# MCU.net
KiCad netlist of a schematic drawn in Altium Designer
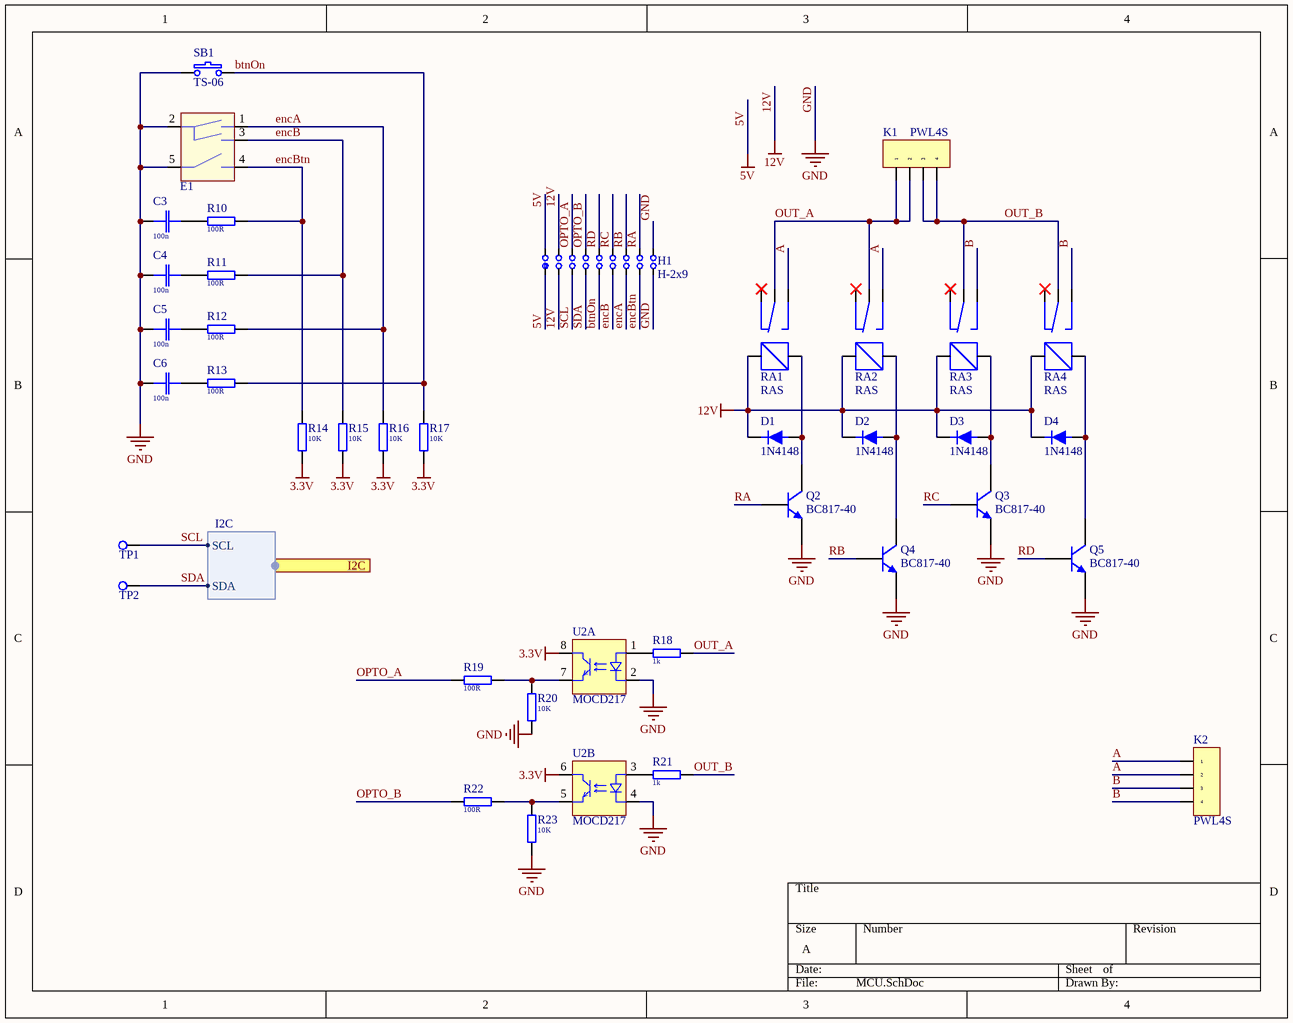
[diagram p0: MCU.SchDoc]

(export (version "E")
  (design (tool "Eeschema 10.0.6"))
  (components
    (comp (ref "C3")
      (value "100n")
      (footprint "C0805(2013)")
      (description "SMD-0805 50V Y5V +80/-20%")
      (libsource (lib "SMD-RCL") (part "C-0805   50V 100n"))
    )
    (comp (ref "C4")
      (value "100n")
      (footprint "C0805(2013)")
      (description "SMD-0805 50V Y5V +80/-20%")
      (libsource (lib "SMD-RCL") (part "C-0805   50V 100n"))
    )
    (comp (ref "C5")
      (value "100n")
      (footprint "C0805(2013)")
      (description "SMD-0805 50V Y5V +80/-20%")
      (libsource (lib "SMD-RCL") (part "C-0805   50V 100n"))
    )
    (comp (ref "C6")
      (value "100n")
      (footprint "C0805(2013)")
      (description "SMD-0805 50V Y5V +80/-20%")
      (libsource (lib "SMD-RCL") (part "C-0805   50V 100n"))
    )
    (comp (ref "D1")
      (value "1N4148")
      (footprint "DO-214AC (SMA)")
      (description "DO-35 75V 0.2A 1uS 4A 4nS")
      (libsource (lib "Diodes") (part "1N4148"))
    )
    (comp (ref "D2")
      (value "1N4148")
      (footprint "DO-214AC (SMA)")
      (description "DO-35 75V 0.2A 1uS 4A 4nS")
      (libsource (lib "Diodes") (part "1N4148"))
    )
    (comp (ref "D3")
      (value "1N4148")
      (footprint "DO-214AC (SMA)")
      (description "DO-35 75V 0.2A 1uS 4A 4nS")
      (libsource (lib "Diodes") (part "1N4148"))
    )
    (comp (ref "D4")
      (value "1N4148")
      (footprint "DO-214AC (SMA)")
      (description "DO-35 75V 0.2A 1uS 4A 4nS")
      (libsource (lib "Diodes") (part "1N4148"))
    )
    (comp (ref "E1")
      (value "Encoder SW")
      (footprint "PEC12")
      (description "Mechanical encoder with switch")
      (fields (field (name "PUBLISHER") "Altium Limited"))
      (libsource (lib "Mechanical") (part "Encoder SW"))
    )
    (comp (ref "H1") (value "H-2x9") (footprint "J2x9") (libsource (lib "Connektor") (part "H-2x9")))
    (comp (ref "K1")
      (value "PWL4S")
      (footprint "PWL4S")
      (description "3.96mm 7A/250V")
      (libsource (lib "Connektor") (part "PWL4S"))
    )
    (comp (ref "K2")
      (value "PWL4S")
      (footprint "PWL4S")
      (description "3.96mm 7A/250V")
      (libsource (lib "") (part "PWL4S_1"))
    )
    (comp (ref "Q2")
      (value "BC817-40")
      (footprint "SOT23_N")
      (description "NPN General-purpose Transistor")
      (fields (field (name "PUBLISHER") "Altium Limited"))
      (libsource (lib "Philips Discrete BJT - Low Power") (part "BC817-40"))
    )
    (comp (ref "Q3")
      (value "BC817-40")
      (footprint "SOT23_N")
      (description "NPN General-purpose Transistor")
      (fields (field (name "PUBLISHER") "Altium Limited"))
      (libsource (lib "Philips Discrete BJT - Low Power") (part "BC817-40"))
    )
    (comp (ref "Q4")
      (value "BC817-40")
      (footprint "SOT23_N")
      (description "NPN General-purpose Transistor")
      (fields (field (name "PUBLISHER") "Altium Limited"))
      (libsource (lib "Philips Discrete BJT - Low Power") (part "BC817-40"))
    )
    (comp (ref "Q5")
      (value "BC817-40")
      (footprint "SOT23_N")
      (description "NPN General-purpose Transistor")
      (fields (field (name "PUBLISHER") "Altium Limited"))
      (libsource (lib "Philips Discrete BJT - Low Power") (part "BC817-40"))
    )
    (comp (ref "R10")
      (value "100R")
      (footprint "R0805")
      (description "SMD 0805 0.1W 5% 150V")
      (libsource (lib "SMD-RCL") (part "R-0805"))
    )
    (comp (ref "R11")
      (value "100R")
      (footprint "R0805")
      (description "SMD 0805 0.1W 5% 150V")
      (libsource (lib "SMD-RCL") (part "R-0805"))
    )
    (comp (ref "R12")
      (value "100R")
      (footprint "R0805")
      (description "SMD 0805 0.1W 5% 150V")
      (libsource (lib "SMD-RCL") (part "R-0805"))
    )
    (comp (ref "R13")
      (value "100R")
      (footprint "R0805")
      (description "SMD 0805 0.1W 5% 150V")
      (libsource (lib "SMD-RCL") (part "R-0805"))
    )
    (comp (ref "R14")
      (value "10K")
      (footprint "R0805")
      (description "SMD 0805 0.1W 5% 150V")
      (libsource (lib "SMD-RCL") (part "R-0805"))
    )
    (comp (ref "R15")
      (value "10K")
      (footprint "R0805")
      (description "SMD 0805 0.1W 5% 150V")
      (libsource (lib "SMD-RCL") (part "R-0805"))
    )
    (comp (ref "R16")
      (value "10K")
      (footprint "R0805")
      (description "SMD 0805 0.1W 5% 150V")
      (libsource (lib "SMD-RCL") (part "R-0805"))
    )
    (comp (ref "R17")
      (value "10K")
      (footprint "R0805")
      (description "SMD 0805 0.1W 5% 150V")
      (libsource (lib "SMD-RCL") (part "R-0805"))
    )
    (comp (ref "R18")
      (value "1k")
      (footprint "R0805")
      (description "SMD 0805 0.1W 5% 150V")
      (libsource (lib "SMD-RCL") (part "R-0805"))
    )
    (comp (ref "R19")
      (value "100R")
      (footprint "R0805")
      (description "SMD 0805 0.1W 5% 150V")
      (libsource (lib "SMD-RCL") (part "R-0805"))
    )
    (comp (ref "R20")
      (value "10K")
      (footprint "R0805")
      (description "SMD 0805 0.1W 5% 150V")
      (libsource (lib "SMD-RCL") (part "R-0805"))
    )
    (comp (ref "R21")
      (value "1k")
      (footprint "R0805")
      (description "SMD 0805 0.1W 5% 150V")
      (libsource (lib "SMD-RCL") (part "R-0805"))
    )
    (comp (ref "R22")
      (value "100R")
      (footprint "R0805")
      (description "SMD 0805 0.1W 5% 150V")
      (libsource (lib "SMD-RCL") (part "R-0805"))
    )
    (comp (ref "R23")
      (value "10K")
      (footprint "R0805")
      (description "SMD 0805 0.1W 5% 150V")
      (libsource (lib "SMD-RCL") (part "R-0805"))
    )
    (comp (ref "RA1")
      (value "RAS")
      (footprint "Rele RAS")
      (description "AC-120V 15A DC-14V 20A 30V 15A /0.36W")
      (libsource (lib "Devise") (part "Relay RAS"))
    )
    (comp (ref "RA2")
      (value "RAS")
      (footprint "Rele RAS")
      (description "AC-120V 15A DC-14V 20A 30V 15A /0.36W")
      (libsource (lib "Devise") (part "Relay RAS"))
    )
    (comp (ref "RA3")
      (value "RAS")
      (footprint "Rele RAS")
      (description "AC-120V 15A DC-14V 20A 30V 15A /0.36W")
      (libsource (lib "Devise") (part "Relay RAS"))
    )
    (comp (ref "RA4")
      (value "RAS")
      (footprint "Rele RAS")
      (description "AC-120V 15A DC-14V 20A 30V 15A /0.36W")
      (libsource (lib "Devise") (part "Relay RAS"))
    )
    (comp (ref "SB1") (value "TS-06") (footprint "TS-06") (libsource (lib "Devise") (part "Buton TS-06")))
    (comp (ref "TP1")
      (value "TP")
      (footprint "TP_TH")
      (description "Test point")
      (libsource (lib "Mechanical") (part "TP"))
    )
    (comp (ref "TP2")
      (value "TP")
      (footprint "TP_TH")
      (description "Test point")
      (libsource (lib "Mechanical") (part "TP"))
    )
    (comp (ref "U2")
      (value "MOCD217")
      (footprint "SO-8 (MOCD217)")
      (description "Dual optocouple")
      (libsource (lib "Opto") (part "MOCD217"))
    )
  )
  (nets
    (net (code "2") (name "/A") (class "Default")
      (node (ref "K2") (pin "1") (pinfunction "1_1") (pintype "passive"))
      (node (ref "K2") (pin "2") (pinfunction "2_2") (pintype "passive"))
      (node (ref "RA1") (pin "5") (pinfunction "NO_5") (pintype "passive"))
      (node (ref "RA2") (pin "5") (pinfunction "NO_5") (pintype "passive"))
    )
    (net (code "3") (name "/B") (class "Default")
      (node (ref "K2") (pin "3") (pinfunction "3_3") (pintype "passive"))
      (node (ref "K2") (pin "4") (pinfunction "4_4") (pintype "passive"))
      (node (ref "RA3") (pin "5") (pinfunction "NO_5") (pintype "passive"))
      (node (ref "RA4") (pin "5") (pinfunction "NO_5") (pintype "passive"))
    )
    (net (code "4") (name "/OPTO_A") (class "Default")
      (node (ref "H1") (pin "6") (pinfunction "6_6") (pintype "passive"))
      (node (ref "R19") (pin "2") (pinfunction "2_2") (pintype "passive"))
    )
    (net (code "5") (name "/OPTO_B") (class "Default")
      (node (ref "H1") (pin "8") (pinfunction "8_8") (pintype "passive"))
      (node (ref "R22") (pin "2") (pinfunction "2_2") (pintype "passive"))
    )
    (net (code "6") (name "/OUT_A") (class "Default")
      (node (ref "K1") (pin "1") (pinfunction "1_1") (pintype "passive"))
      (node (ref "K1") (pin "2") (pinfunction "2_2") (pintype "passive"))
      (node (ref "R18") (pin "1") (pinfunction "1_1") (pintype "passive"))
      (node (ref "RA1") (pin "4") (pinfunction "O_4") (pintype "passive"))
      (node (ref "RA2") (pin "4") (pinfunction "O_4") (pintype "passive"))
    )
    (net (code "7") (name "/OUT_B") (class "Default")
      (node (ref "K1") (pin "3") (pinfunction "3_3") (pintype "passive"))
      (node (ref "K1") (pin "4") (pinfunction "4_4") (pintype "passive"))
      (node (ref "R21") (pin "1") (pinfunction "1_1") (pintype "passive"))
      (node (ref "RA3") (pin "4") (pinfunction "O_4") (pintype "passive"))
      (node (ref "RA4") (pin "4") (pinfunction "O_4") (pintype "passive"))
    )
    (net (code "8") (name "/RA") (class "Default")
      (node (ref "H1") (pin "16") (pinfunction "16_16") (pintype "passive"))
      (node (ref "Q2") (pin "1") (pinfunction "B_1") (pintype "passive"))
    )
    (net (code "9") (name "/RB") (class "Default")
      (node (ref "H1") (pin "14") (pinfunction "14_14") (pintype "passive"))
      (node (ref "Q4") (pin "1") (pinfunction "B_1") (pintype "passive"))
    )
    (net (code "10") (name "/RC") (class "Default")
      (node (ref "H1") (pin "12") (pinfunction "12_12") (pintype "passive"))
      (node (ref "Q3") (pin "1") (pinfunction "B_1") (pintype "passive"))
    )
    (net (code "11") (name "/RD") (class "Default")
      (node (ref "H1") (pin "10") (pinfunction "10_10") (pintype "passive"))
      (node (ref "Q5") (pin "1") (pinfunction "B_1") (pintype "passive"))
    )
    (net (code "12") (name "/SCL") (class "Default")
      (node (ref "H1") (pin "5") (pinfunction "5_5") (pintype "passive"))
      (node (ref "TP1") (pin "1") (pintype "passive"))
    )
    (net (code "13") (name "/SDA") (class "Default")
      (node (ref "H1") (pin "7") (pinfunction "7_7") (pintype "passive"))
      (node (ref "TP2") (pin "1") (pintype "passive"))
    )
    (net (code "14") (name "/btnOn") (class "Default")
      (node (ref "H1") (pin "9") (pinfunction "9_9") (pintype "passive"))
      (node (ref "R13") (pin "1") (pinfunction "1_1") (pintype "passive"))
      (node (ref "R17") (pin "2") (pinfunction "2_2") (pintype "passive"))
      (node (ref "SB1") (pin "2") (pinfunction "2_2") (pintype "passive"))
    )
    (net (code "15") (name "/encA") (class "Default")
      (node (ref "E1") (pin "1") (pinfunction "1_1") (pintype "passive"))
      (node (ref "H1") (pin "13") (pinfunction "13_13") (pintype "passive"))
      (node (ref "R12") (pin "1") (pinfunction "1_1") (pintype "passive"))
      (node (ref "R16") (pin "2") (pinfunction "2_2") (pintype "passive"))
    )
    (net (code "16") (name "/encB") (class "Default")
      (node (ref "E1") (pin "3") (pinfunction "3_3") (pintype "passive"))
      (node (ref "H1") (pin "11") (pinfunction "11_11") (pintype "passive"))
      (node (ref "R11") (pin "1") (pinfunction "1_1") (pintype "passive"))
      (node (ref "R15") (pin "2") (pinfunction "2_2") (pintype "passive"))
    )
    (net (code "17") (name "/encBtn") (class "Default")
      (node (ref "E1") (pin "4") (pinfunction "4_4") (pintype "passive"))
      (node (ref "H1") (pin "15") (pinfunction "15_15") (pintype "passive"))
      (node (ref "R10") (pin "1") (pinfunction "1_1") (pintype "passive"))
      (node (ref "R14") (pin "2") (pinfunction "2_2") (pintype "passive"))
    )
    (net (code "19") (name "3.3V") (class "Default")
      (node (ref "R14") (pin "1") (pinfunction "1_1") (pintype "passive"))
      (node (ref "R15") (pin "1") (pinfunction "1_1") (pintype "passive"))
      (node (ref "R16") (pin "1") (pinfunction "1_1") (pintype "passive"))
      (node (ref "R17") (pin "1") (pinfunction "1_1") (pintype "passive"))
      (node (ref "U2") (pin "6") (pinfunction "C_6") (pintype "passive"))
      (node (ref "U2") (pin "8") (pinfunction "C_8") (pintype "passive"))
    )
    (net (code "20") (name "5V") (class "Default")
      (node (ref "H1") (pin "1") (pinfunction "1_1") (pintype "passive"))
      (node (ref "H1") (pin "2") (pinfunction "2_2") (pintype "passive"))
    )
    (net (code "21") (name "12V") (class "Default")
      (node (ref "D1") (pin "2") (pinfunction "C_2") (pintype "passive"))
      (node (ref "D2") (pin "2") (pinfunction "C_2") (pintype "passive"))
      (node (ref "D3") (pin "2") (pinfunction "C_2") (pintype "passive"))
      (node (ref "D4") (pin "2") (pinfunction "C_2") (pintype "passive"))
      (node (ref "H1") (pin "3") (pinfunction "3_3") (pintype "passive"))
      (node (ref "H1") (pin "4") (pinfunction "4_4") (pintype "passive"))
      (node (ref "RA1") (pin "1") (pinfunction "a_1") (pintype "passive"))
      (node (ref "RA2") (pin "1") (pinfunction "a_1") (pintype "passive"))
      (node (ref "RA3") (pin "1") (pinfunction "a_1") (pintype "passive"))
      (node (ref "RA4") (pin "1") (pinfunction "a_1") (pintype "passive"))
    )
    (net (code "22") (name "GND") (class "Default")
      (node (ref "C3") (pin "2") (pinfunction "2_2") (pintype "passive"))
      (node (ref "C4") (pin "2") (pinfunction "2_2") (pintype "passive"))
      (node (ref "C5") (pin "2") (pinfunction "2_2") (pintype "passive"))
      (node (ref "C6") (pin "2") (pinfunction "2_2") (pintype "passive"))
      (node (ref "E1") (pin "2") (pinfunction "2_2") (pintype "passive"))
      (node (ref "E1") (pin "5") (pinfunction "5_5") (pintype "passive"))
      (node (ref "H1") (pin "17") (pinfunction "17_17") (pintype "passive"))
      (node (ref "H1") (pin "18") (pinfunction "18_18") (pintype "passive"))
      (node (ref "Q2") (pin "2") (pinfunction "E_2") (pintype "passive"))
      (node (ref "Q3") (pin "2") (pinfunction "E_2") (pintype "passive"))
      (node (ref "Q4") (pin "2") (pinfunction "E_2") (pintype "passive"))
      (node (ref "Q5") (pin "2") (pinfunction "E_2") (pintype "passive"))
      (node (ref "R20") (pin "2") (pinfunction "2_2") (pintype "passive"))
      (node (ref "R23") (pin "1") (pinfunction "1_1") (pintype "passive"))
      (node (ref "SB1") (pin "1") (pinfunction "1_1") (pintype "passive"))
      (node (ref "U2") (pin "2") (pinfunction "K_2") (pintype "passive"))
      (node (ref "U2") (pin "4") (pinfunction "K_4") (pintype "passive"))
    )
    (net (code "23") (name "Net-(C3-Pad1)") (class "Default")
      (node (ref "C3") (pin "1") (pinfunction "1_1") (pintype "passive"))
      (node (ref "R10") (pin "2") (pinfunction "2_2") (pintype "passive"))
    )
    (net (code "24") (name "Net-(C4-Pad1)") (class "Default")
      (node (ref "C4") (pin "1") (pinfunction "1_1") (pintype "passive"))
      (node (ref "R11") (pin "2") (pinfunction "2_2") (pintype "passive"))
    )
    (net (code "25") (name "Net-(C5-Pad1)") (class "Default")
      (node (ref "C5") (pin "1") (pinfunction "1_1") (pintype "passive"))
      (node (ref "R12") (pin "2") (pinfunction "2_2") (pintype "passive"))
    )
    (net (code "26") (name "Net-(C6-Pad1)") (class "Default")
      (node (ref "C6") (pin "1") (pinfunction "1_1") (pintype "passive"))
      (node (ref "R13") (pin "2") (pinfunction "2_2") (pintype "passive"))
    )
    (net (code "27") (name "Net-(D1-A)") (class "Default")
      (node (ref "D1") (pin "1") (pinfunction "A_1") (pintype "passive"))
      (node (ref "Q2") (pin "3") (pinfunction "C_3") (pintype "passive"))
      (node (ref "RA1") (pin "2") (pinfunction "b_2") (pintype "passive"))
    )
    (net (code "28") (name "Net-(D2-A)") (class "Default")
      (node (ref "D2") (pin "1") (pinfunction "A_1") (pintype "passive"))
      (node (ref "Q4") (pin "3") (pinfunction "C_3") (pintype "passive"))
      (node (ref "RA2") (pin "2") (pinfunction "b_2") (pintype "passive"))
    )
    (net (code "29") (name "Net-(D3-A)") (class "Default")
      (node (ref "D3") (pin "1") (pinfunction "A_1") (pintype "passive"))
      (node (ref "Q3") (pin "3") (pinfunction "C_3") (pintype "passive"))
      (node (ref "RA3") (pin "2") (pinfunction "b_2") (pintype "passive"))
    )
    (net (code "30") (name "Net-(D4-A)") (class "Default")
      (node (ref "D4") (pin "1") (pinfunction "A_1") (pintype "passive"))
      (node (ref "Q5") (pin "3") (pinfunction "C_3") (pintype "passive"))
      (node (ref "RA4") (pin "2") (pinfunction "b_2") (pintype "passive"))
    )
    (net (code "31") (name "Net-(U2A-A)") (class "Default")
      (node (ref "R18") (pin "2") (pinfunction "2_2") (pintype "passive"))
      (node (ref "U2") (pin "1") (pinfunction "A_1") (pintype "passive"))
    )
    (net (code "32") (name "Net-(U2A-E)") (class "Default")
      (node (ref "R19") (pin "1") (pinfunction "1_1") (pintype "passive"))
      (node (ref "R20") (pin "1") (pinfunction "1_1") (pintype "passive"))
      (node (ref "U2") (pin "7") (pinfunction "E_7") (pintype "passive"))
    )
    (net (code "33") (name "Net-(U2B-A)") (class "Default")
      (node (ref "R21") (pin "2") (pinfunction "2_2") (pintype "passive"))
      (node (ref "U2") (pin "3") (pinfunction "A_3") (pintype "passive"))
    )
    (net (code "34") (name "Net-(U2B-E)") (class "Default")
      (node (ref "R22") (pin "1") (pinfunction "1_1") (pintype "passive"))
      (node (ref "R23") (pin "2") (pinfunction "2_2") (pintype "passive"))
      (node (ref "U2") (pin "5") (pinfunction "E_5") (pintype "passive"))
    )
    (net (code "35") (name "unconnected-(RA1-NC-Pad3)") (class "Default")
      (node (ref "RA1") (pin "3") (pinfunction "NC_3") (pintype "passive+no_connect"))
    )
    (net (code "36") (name "unconnected-(RA2-NC-Pad3)") (class "Default")
      (node (ref "RA2") (pin "3") (pinfunction "NC_3") (pintype "passive+no_connect"))
    )
    (net (code "37") (name "unconnected-(RA3-NC-Pad3)") (class "Default")
      (node (ref "RA3") (pin "3") (pinfunction "NC_3") (pintype "passive+no_connect"))
    )
    (net (code "38") (name "unconnected-(RA4-NC-Pad3)") (class "Default")
      (node (ref "RA4") (pin "3") (pinfunction "NC_3") (pintype "passive+no_connect"))
    )
  )
)
